# Sensors.net
KiCad netlist of a schematic drawn in Altium Designer
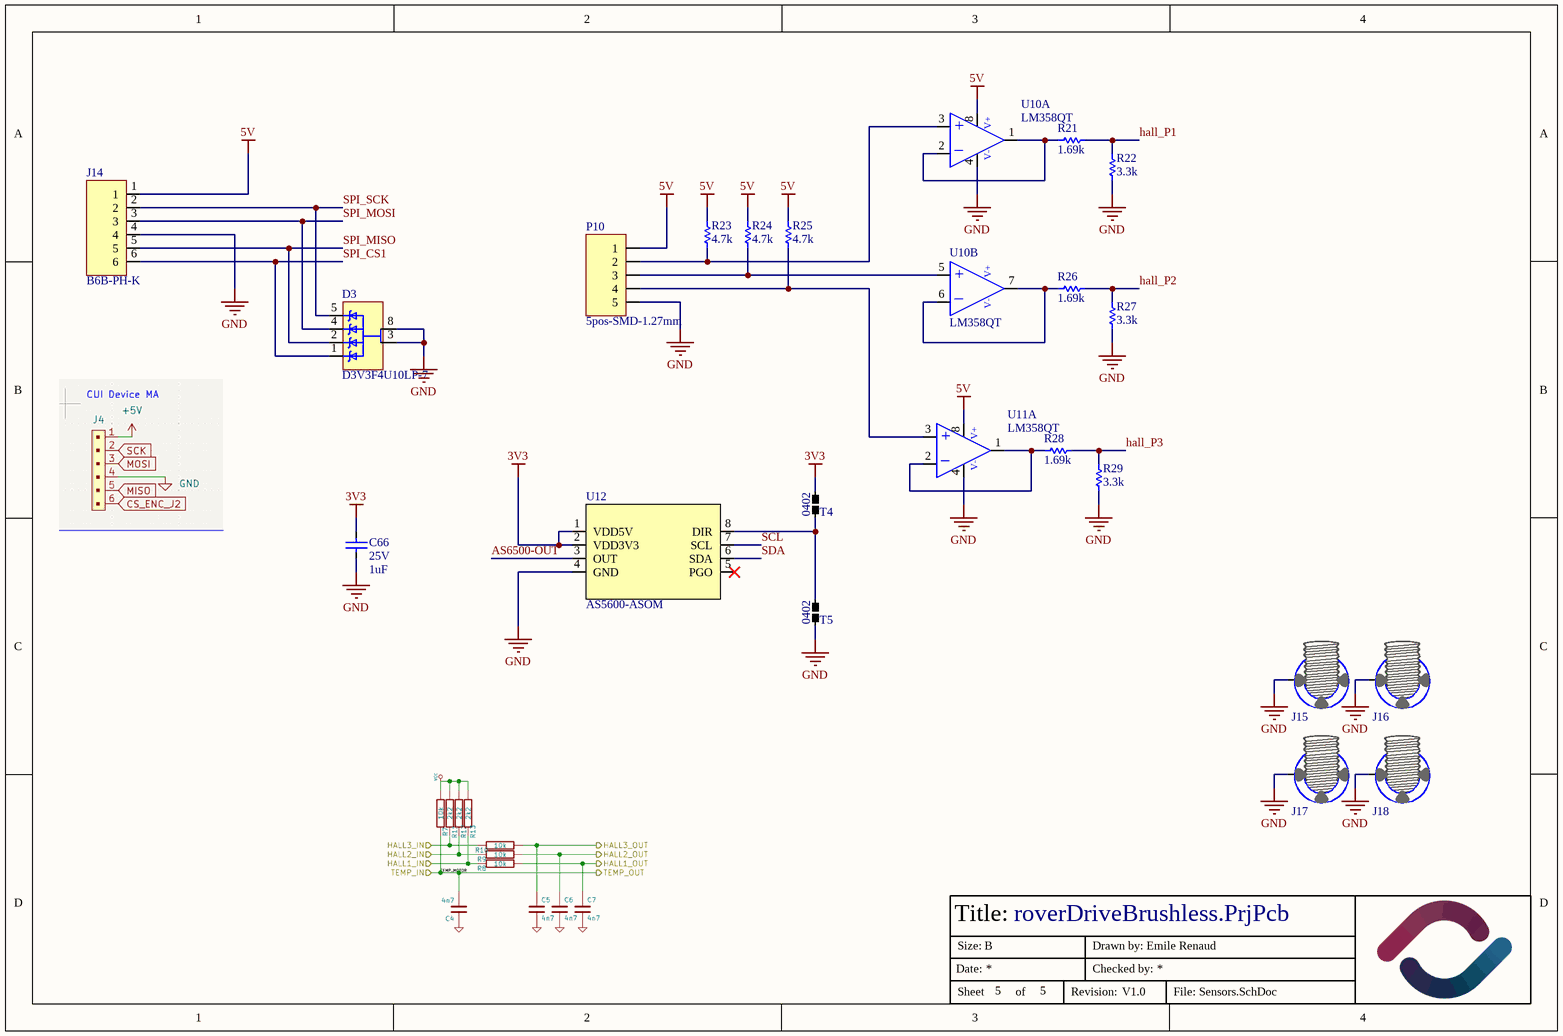
[diagram p0: Sensors.SchDoc]

(export (version "E")
  (design (tool "Eeschema 10.0.6"))
  (components
    (comp (ref "C66")
      (value "1uF")
      (footprint "CAPACITOR-0603")
      (description "Capacitor-0603-1uF-25V-X5R")
      (fields (field (name "VOLT") "25V"))
      (libsource (lib "Capacitors") (part "Capacitor-0603-1uF-25V-X5R"))
    )
    (comp (ref "D3")
      (value "D3V3F4U10LP-7")
      (footprint "U-DFN2510-10")
      (description "5V (Typ) Clamp 5A (8/20µs) Ipp Tvs Diode Surface Mount U-DFN2510-10")
      (libsource (lib "diodes-tvs") (part "D3V3F4U10LP-7"))
    )
    (comp (ref "J14")
      (value "B6B-PH-K")
      (footprint "B6B-PH-K")
      (description "JST, TH, 6 position 0.079\" (2.00mm)")
      (libsource (lib "JST") (part "B6B-PH-K"))
    )
    (comp (ref "J15")
      (value "hole")
      (footprint "HOLE-3.40MM-M3-7MMEYELET-MountingFeature")
      (description "Hole for M3 Bolt with 7mm pad")
      (libsource (lib "JumpersAndHoles") (part "Hole 3.40mm M3-MountingFeature"))
    )
    (comp (ref "J16")
      (value "hole")
      (footprint "HOLE-3.40MM-M3-7MMEYELET-MountingFeature")
      (description "Hole for M3 Bolt with 7mm pad")
      (libsource (lib "JumpersAndHoles") (part "Hole 3.40mm M3-MountingFeature"))
    )
    (comp (ref "J17")
      (value "hole")
      (footprint "HOLE-3.40MM-M3-7MMEYELET-MountingFeature")
      (description "Hole for M3 Bolt with 7mm pad")
      (libsource (lib "JumpersAndHoles") (part "Hole 3.40mm M3-MountingFeature"))
    )
    (comp (ref "J18")
      (value "hole")
      (footprint "HOLE-3.40MM-M3-7MMEYELET-MountingFeature")
      (description "Hole for M3 Bolt with 7mm pad")
      (libsource (lib "JumpersAndHoles") (part "Hole 3.40mm M3-MountingFeature"))
    )
    (comp (ref "P10")
      (value "5pos-SMD-1.27mm")
      (footprint "HDR1X5-SMD-50mils-SILK")
      (libsource (lib "Header") (part "5pos-SMD-1.27mm"))
    )
    (comp (ref "R21")
      (value "1.69k")
      (footprint "Resistor-0603")
      (description "Resistor0603-1.69k")
      (fields (field (name "Comment") "SMT resistor"))
      (libsource (lib "Resistors") (part "Resistor-0603-1.69k"))
    )
    (comp (ref "R22")
      (value "3.3k")
      (footprint "Resistor-0603")
      (description "Resistor0603-3.3k")
      (fields (field (name "Comment") "SMT resistor"))
      (libsource (lib "Resistors") (part "Resistor-0603-3.3k"))
    )
    (comp (ref "R23")
      (value "4.7k")
      (footprint "Resistor-0603")
      (description "Resistor0603-4.7k")
      (fields (field (name "Comment") "SMT resistor"))
      (libsource (lib "Resistors") (part "Resistor-0603-4.7k"))
    )
    (comp (ref "R24")
      (value "4.7k")
      (footprint "Resistor-0603")
      (description "Resistor0603-4.7k")
      (fields (field (name "Comment") "SMT resistor"))
      (libsource (lib "Resistors") (part "Resistor-0603-4.7k"))
    )
    (comp (ref "R25")
      (value "4.7k")
      (footprint "Resistor-0603")
      (description "Resistor0603-4.7k")
      (fields (field (name "Comment") "SMT resistor"))
      (libsource (lib "Resistors") (part "Resistor-0603-4.7k"))
    )
    (comp (ref "R26")
      (value "1.69k")
      (footprint "Resistor-0603")
      (description "Resistor0603-1.69k")
      (fields (field (name "Comment") "SMT resistor"))
      (libsource (lib "Resistors") (part "Resistor-0603-1.69k"))
    )
    (comp (ref "R27")
      (value "3.3k")
      (footprint "Resistor-0603")
      (description "Resistor0603-3.3k")
      (fields (field (name "Comment") "SMT resistor"))
      (libsource (lib "Resistors") (part "Resistor-0603-3.3k"))
    )
    (comp (ref "R28")
      (value "1.69k")
      (footprint "Resistor-0603")
      (description "Resistor0603-1.69k")
      (fields (field (name "Comment") "SMT resistor"))
      (libsource (lib "Resistors") (part "Resistor-0603-1.69k"))
    )
    (comp (ref "R29")
      (value "3.3k")
      (footprint "Resistor-0603")
      (description "Resistor0603-3.3k")
      (fields (field (name "Comment") "SMT resistor"))
      (libsource (lib "Resistors") (part "Resistor-0603-3.3k"))
    )
    (comp (ref "T4")
      (value "NetTie_0402")
      (footprint "NetTie-0402")
      (libsource (lib "JumpersAndHoles") (part "NetTie_0402"))
    )
    (comp (ref "T5")
      (value "NetTie_0402")
      (footprint "NetTie-0402")
      (libsource (lib "JumpersAndHoles") (part "NetTie_0402"))
    )
    (comp (ref "U10")
      (value "LM358QT")
      (footprint "DFN8-2x2")
      (description "General Purpose Amplifier 2 Circuit 8-DFN (2x2)")
      (libsource (lib "OperationalAmplifiers") (part "LM358QT"))
    )
    (comp (ref "U11")
      (value "LM358QT")
      (footprint "DFN8-2x2")
      (description "General Purpose Amplifier 2 Circuit 8-DFN (2x2)")
      (libsource (lib "OperationalAmplifiers") (part "LM358QT"))
    )
    (comp (ref "U12")
      (value "AS5600-ASOM")
      (footprint "AS5600L-ASOM_AMS")
      (description "SENSOR ANGLE 360DEG SMD")
      (fields
        (field (name "MANUFACTURER_PART_NUMBER") "AS5600L-ASOM")
        (field (name "COPYRIGHT") "Copyright (C) 2023 Ultra Librarian. All rights reserved.")
      )
      (libsource (lib "Encoder") (part "AS5600-ASOM"))
    )
  )
  (nets
    (net (code "1") (name "/AS6500-OUT") (class "Default")
      (node (ref "U12") (pin "3") (pinfunction "OUT_3") (pintype "passive"))
    )
    (net (code "2") (name "/SCL") (class "Default")
      (node (ref "U12") (pin "7") (pinfunction "SCL_7") (pintype "passive"))
    )
    (net (code "3") (name "/SDA") (class "Default")
      (node (ref "U12") (pin "6") (pinfunction "SDA_6") (pintype "passive"))
    )
    (net (code "4") (name "/SPI_CS1") (class "Default")
      (node (ref "D3") (pin "1") (pinfunction "L2_1") (pintype "passive"))
      (node (ref "J14") (pin "6") (pinfunction "6_6") (pintype "passive"))
    )
    (net (code "5") (name "/SPI_MISO") (class "Default")
      (node (ref "D3") (pin "2") (pinfunction "GND_2") (pintype "passive"))
      (node (ref "J14") (pin "5") (pinfunction "5_5") (pintype "passive"))
    )
    (net (code "6") (name "/SPI_MOSI") (class "Default")
      (node (ref "D3") (pin "4") (pinfunction "L4_4") (pintype "passive"))
      (node (ref "J14") (pin "3") (pinfunction "3_3") (pintype "passive"))
    )
    (net (code "7") (name "/SPI_SCK") (class "Default")
      (node (ref "D3") (pin "5") (pinfunction "VDD_5") (pintype "passive"))
      (node (ref "J14") (pin "2") (pinfunction "2_2") (pintype "passive"))
    )
    (net (code "8") (name "/hall_P1") (class "Default")
      (node (ref "R21") (pin "2") (pinfunction "2_2") (pintype "passive"))
      (node (ref "R22") (pin "2") (pinfunction "2_2") (pintype "passive"))
    )
    (net (code "9") (name "/hall_P2") (class "Default")
      (node (ref "R26") (pin "2") (pinfunction "2_2") (pintype "passive"))
      (node (ref "R27") (pin "2") (pinfunction "2_2") (pintype "passive"))
    )
    (net (code "10") (name "/hall_P3") (class "Default")
      (node (ref "R28") (pin "2") (pinfunction "2_2") (pintype "passive"))
      (node (ref "R29") (pin "2") (pinfunction "2_2") (pintype "passive"))
    )
    (net (code "11") (name "3V3") (class "Default")
      (node (ref "C66") (pin "2") (pinfunction "2_2") (pintype "passive"))
      (node (ref "T4") (pin "1") (pinfunction "1_1") (pintype "passive"))
      (node (ref "U12") (pin "1") (pinfunction "VDD5V_1") (pintype "passive"))
      (node (ref "U12") (pin "2") (pinfunction "VDD3V3_2") (pintype "passive"))
    )
    (net (code "12") (name "5V") (class "Default")
      (node (ref "J14") (pin "1") (pinfunction "1_1") (pintype "passive"))
      (node (ref "P10") (pin "1") (pinfunction "1_1") (pintype "passive"))
      (node (ref "R23") (pin "2") (pinfunction "2_2") (pintype "passive"))
      (node (ref "R24") (pin "2") (pinfunction "2_2") (pintype "passive"))
      (node (ref "R25") (pin "2") (pinfunction "2_2") (pintype "passive"))
      (node (ref "U10") (pin "8") (pinfunction "VS+_8") (pintype "passive"))
      (node (ref "U11") (pin "8") (pinfunction "VS+_8") (pintype "passive"))
    )
    (net (code "13") (name "GND") (class "Default")
      (node (ref "C66") (pin "1") (pinfunction "1_1") (pintype "passive"))
      (node (ref "D3") (pin "3") (pinfunction "L3_3") (pintype "passive"))
      (node (ref "D3") (pin "8") (pinfunction "L4_8") (pintype "passive"))
      (node (ref "J14") (pin "4") (pinfunction "4_4") (pintype "passive"))
      (node (ref "J15") (pin "1") (pinfunction "1_1") (pintype "passive"))
      (node (ref "J16") (pin "1") (pinfunction "1_1") (pintype "passive"))
      (node (ref "J17") (pin "1") (pinfunction "1_1") (pintype "passive"))
      (node (ref "J18") (pin "1") (pinfunction "1_1") (pintype "passive"))
      (node (ref "P10") (pin "5") (pinfunction "5_5") (pintype "passive"))
      (node (ref "R22") (pin "1") (pinfunction "1_1") (pintype "passive"))
      (node (ref "R27") (pin "1") (pinfunction "1_1") (pintype "passive"))
      (node (ref "R29") (pin "1") (pinfunction "1_1") (pintype "passive"))
      (node (ref "T5") (pin "2") (pinfunction "2_2") (pintype "passive"))
      (node (ref "U10") (pin "4") (pinfunction "VS-_4") (pintype "passive"))
      (node (ref "U11") (pin "4") (pinfunction "VS-_4") (pintype "passive"))
      (node (ref "U12") (pin "4") (pinfunction "GND_4") (pintype "passive"))
    )
    (net (code "14") (name "Net-(U10A-IN1+)") (class "Default")
      (node (ref "P10") (pin "2") (pinfunction "2_2") (pintype "passive"))
      (node (ref "R23") (pin "1") (pinfunction "1_1") (pintype "passive"))
      (node (ref "U10") (pin "3") (pinfunction "IN1+_3") (pintype "passive"))
    )
    (net (code "15") (name "Net-(U10A-IN1-)") (class "Default")
      (node (ref "R21") (pin "1") (pinfunction "1_1") (pintype "passive"))
      (node (ref "U10") (pin "1") (pinfunction "OUT1_1") (pintype "passive"))
      (node (ref "U10") (pin "2") (pinfunction "IN1-_2") (pintype "passive"))
    )
    (net (code "16") (name "Net-(U10B-IN2+)") (class "Default")
      (node (ref "P10") (pin "3") (pinfunction "3_3") (pintype "passive"))
      (node (ref "R24") (pin "1") (pinfunction "1_1") (pintype "passive"))
      (node (ref "U10") (pin "5") (pinfunction "IN2+_5") (pintype "passive"))
    )
    (net (code "17") (name "Net-(U10B-IN2-)") (class "Default")
      (node (ref "R26") (pin "1") (pinfunction "1_1") (pintype "passive"))
      (node (ref "U10") (pin "6") (pinfunction "IN2-_6") (pintype "passive"))
      (node (ref "U10") (pin "7") (pinfunction "OUT2_7") (pintype "passive"))
    )
    (net (code "18") (name "Net-(U11A-IN1+)") (class "Default")
      (node (ref "P10") (pin "4") (pinfunction "4_4") (pintype "passive"))
      (node (ref "R25") (pin "1") (pinfunction "1_1") (pintype "passive"))
      (node (ref "U11") (pin "3") (pinfunction "IN1+_3") (pintype "passive"))
    )
    (net (code "19") (name "Net-(U11A-IN1-)") (class "Default")
      (node (ref "R28") (pin "1") (pinfunction "1_1") (pintype "passive"))
      (node (ref "U11") (pin "1") (pinfunction "OUT1_1") (pintype "passive"))
      (node (ref "U11") (pin "2") (pinfunction "IN1-_2") (pintype "passive"))
    )
    (net (code "20") (name "Net-(U12-DIR)") (class "Default")
      (node (ref "T4") (pin "2") (pinfunction "2_2") (pintype "passive"))
      (node (ref "T5") (pin "1") (pinfunction "1_1") (pintype "passive"))
      (node (ref "U12") (pin "8") (pinfunction "DIR_8") (pintype "passive"))
    )
    (net (code "21") (name "unconnected-(U12-PGO-Pad5)") (class "Default")
      (node (ref "U12") (pin "5") (pinfunction "PGO_5") (pintype "passive+no_connect"))
    )
  )
)
